# minx_ajh_1_1.net
KiCad netlist of a schematic drawn in EAGLE
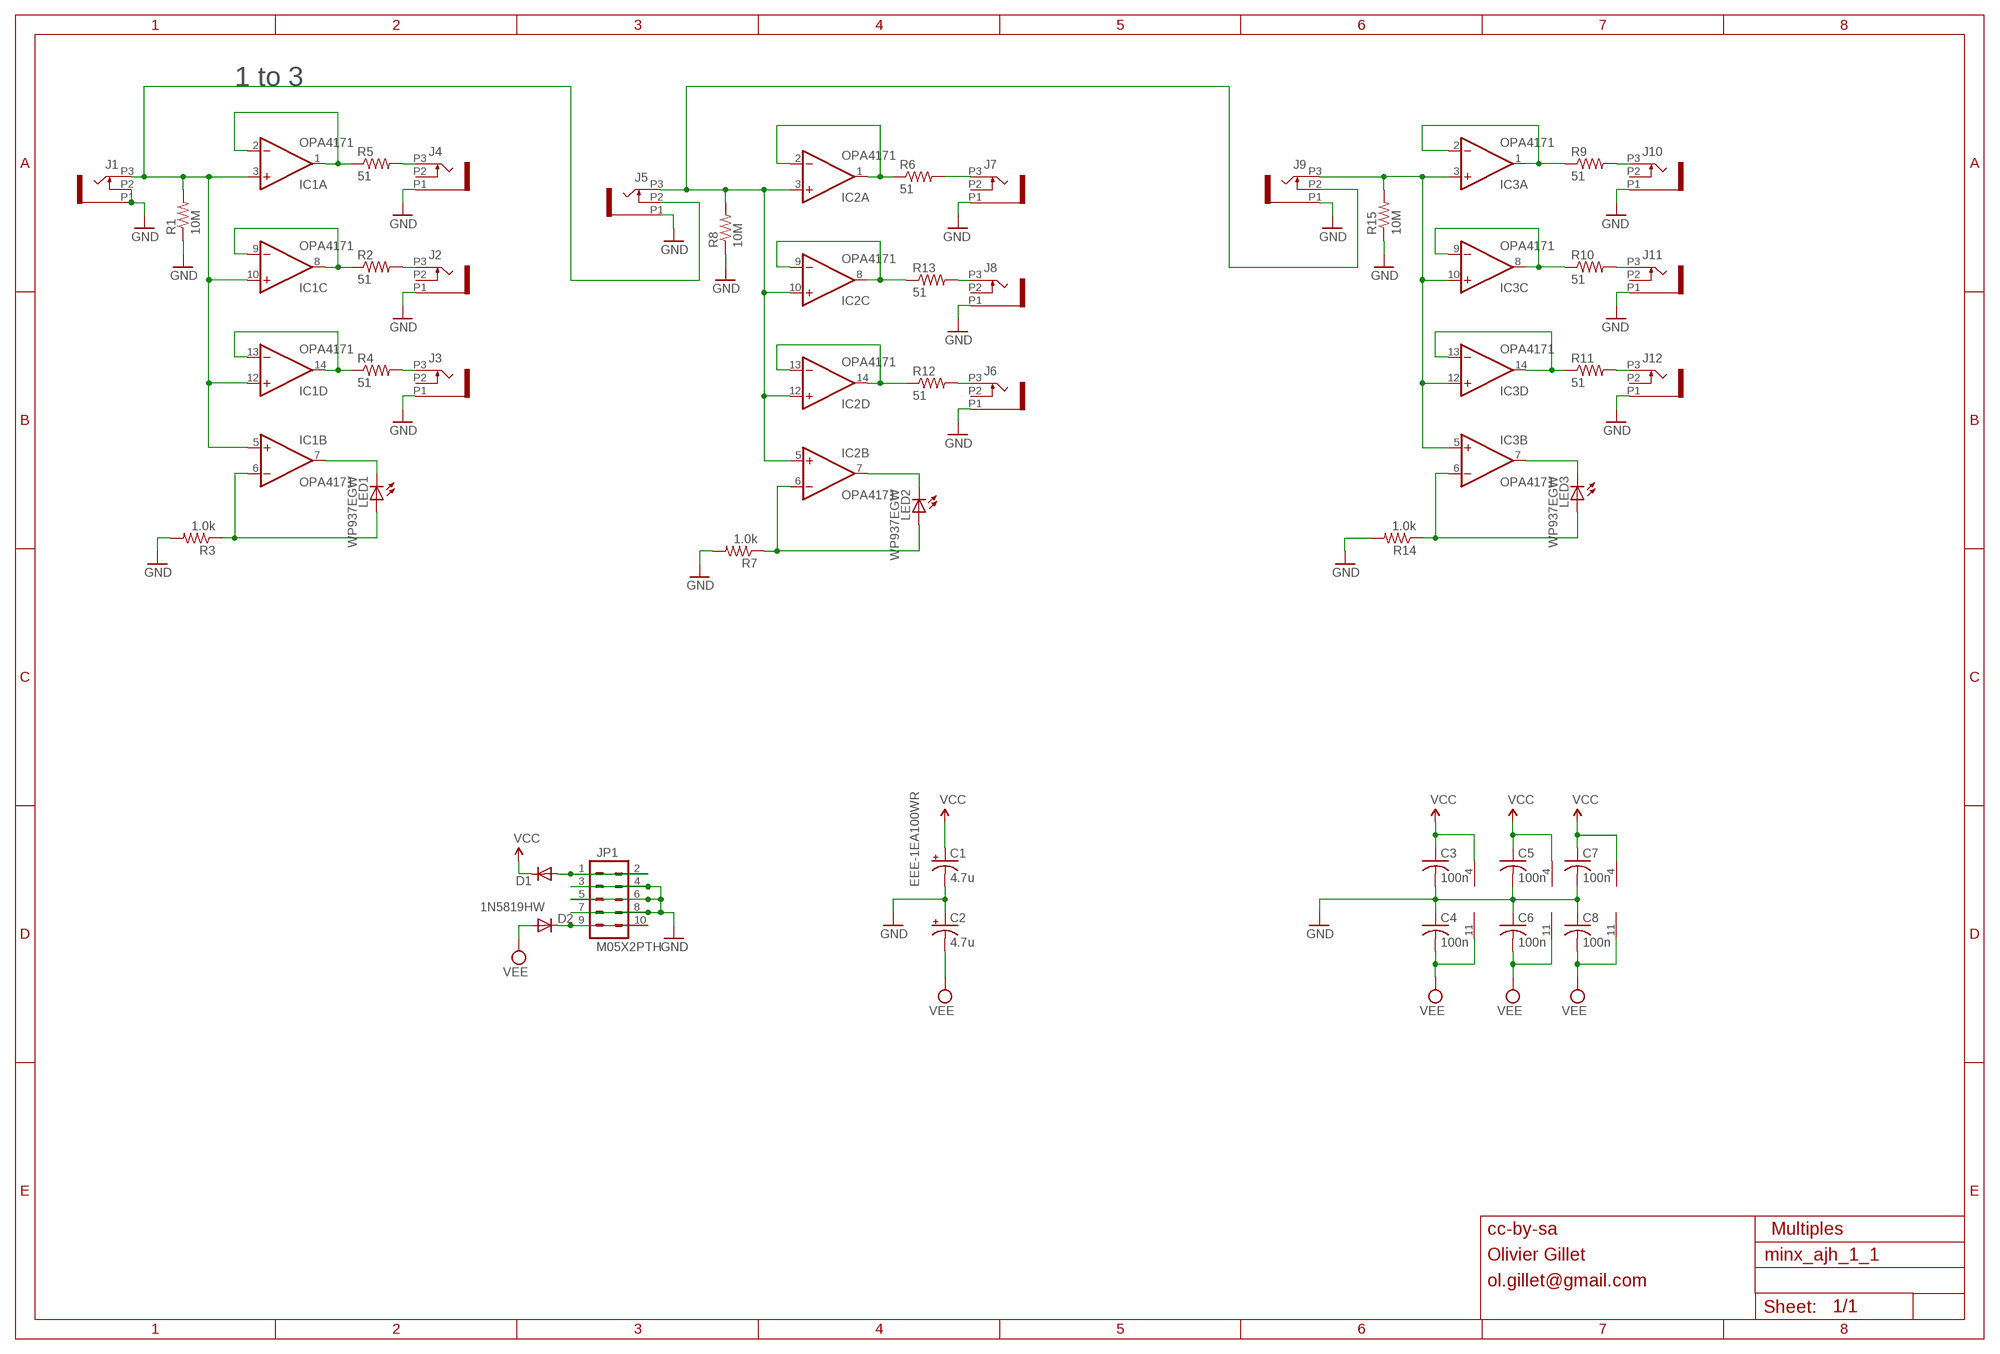
[diagram p0: schematic, sheet 1]

(export (version "E")
  (design (tool "Eeschema 10.0.6"))
  (components
    (comp (ref "C1")
      (value "4.7u")
      (footprint "eagle-import:PANASONIC_A")
      (libsource (lib "eagle-import") (part "CPOL-USA"))
    )
    (comp (ref "C2")
      (value "4.7u")
      (footprint "eagle-import:PANASONIC_A")
      (libsource (lib "eagle-import") (part "CPOL-USA"))
    )
    (comp (ref "C3")
      (value "100n")
      (footprint "eagle-import:C0603")
      (libsource (lib "eagle-import") (part "C-USC0603"))
    )
    (comp (ref "C4")
      (value "100n")
      (footprint "eagle-import:C0603")
      (libsource (lib "eagle-import") (part "C-USC0603"))
    )
    (comp (ref "C5")
      (value "100n")
      (footprint "eagle-import:C0603")
      (libsource (lib "eagle-import") (part "C-USC0603"))
    )
    (comp (ref "C6")
      (value "100n")
      (footprint "eagle-import:C0603")
      (libsource (lib "eagle-import") (part "C-USC0603"))
    )
    (comp (ref "C7")
      (value "100n")
      (footprint "eagle-import:C0603")
      (libsource (lib "eagle-import") (part "C-USC0603"))
    )
    (comp (ref "C8")
      (value "100n")
      (footprint "eagle-import:C0603")
      (libsource (lib "eagle-import") (part "C-USC0603"))
    )
    (comp (ref "D1")
      (value "1N5819HW")
      (footprint "eagle-import:SOD123")
      (libsource (lib "eagle-import") (part "DIODE-SOD123"))
    )
    (comp (ref "D2")
      (value "1N5819HW")
      (footprint "eagle-import:SOD123")
      (libsource (lib "eagle-import") (part "DIODE-SOD123"))
    )
    (comp (ref "IC1")
      (value "OPA4171")
      (footprint "eagle-import:TSSOP14")
      (libsource (lib "eagle-import") (part "TL074PW"))
    )
    (comp (ref "IC2")
      (value "OPA4171")
      (footprint "eagle-import:TSSOP14")
      (libsource (lib "eagle-import") (part "TL074PW"))
    )
    (comp (ref "IC3")
      (value "OPA4171")
      (footprint "eagle-import:TSSOP14")
      (libsource (lib "eagle-import") (part "TL074PW"))
    )
    (comp (ref "J1")
      (value "PJ301_THONKICONN6")
      (footprint "eagle-import:WQP_PJ_301M6")
      (libsource (lib "eagle-import") (part "PJ301_THONKICONN6"))
    )
    (comp (ref "J2")
      (value "PJ301_THONKICONN6")
      (footprint "eagle-import:WQP_PJ_301M6")
      (libsource (lib "eagle-import") (part "PJ301_THONKICONN6"))
    )
    (comp (ref "J3")
      (value "PJ301_THONKICONN6")
      (footprint "eagle-import:WQP_PJ_301M6")
      (libsource (lib "eagle-import") (part "PJ301_THONKICONN6"))
    )
    (comp (ref "J4")
      (value "PJ301_THONKICONN6")
      (footprint "eagle-import:WQP_PJ_301M6")
      (libsource (lib "eagle-import") (part "PJ301_THONKICONN6"))
    )
    (comp (ref "J5")
      (value "PJ301_THONKICONN6")
      (footprint "eagle-import:WQP_PJ_301M6")
      (libsource (lib "eagle-import") (part "PJ301_THONKICONN6"))
    )
    (comp (ref "J6")
      (value "PJ301_THONKICONN6")
      (footprint "eagle-import:WQP_PJ_301M6")
      (libsource (lib "eagle-import") (part "PJ301_THONKICONN6"))
    )
    (comp (ref "J7")
      (value "PJ301_THONKICONN6")
      (footprint "eagle-import:WQP_PJ_301M6")
      (libsource (lib "eagle-import") (part "PJ301_THONKICONN6"))
    )
    (comp (ref "J8")
      (value "PJ301_THONKICONN6")
      (footprint "eagle-import:WQP_PJ_301M6")
      (libsource (lib "eagle-import") (part "PJ301_THONKICONN6"))
    )
    (comp (ref "J9")
      (value "PJ301_THONKICONN6")
      (footprint "eagle-import:WQP_PJ_301M6")
      (libsource (lib "eagle-import") (part "PJ301_THONKICONN6"))
    )
    (comp (ref "J10")
      (value "PJ301_THONKICONN6")
      (footprint "eagle-import:WQP_PJ_301M6")
      (libsource (lib "eagle-import") (part "PJ301_THONKICONN6"))
    )
    (comp (ref "J11")
      (value "PJ301_THONKICONN6")
      (footprint "eagle-import:WQP_PJ_301M6")
      (libsource (lib "eagle-import") (part "PJ301_THONKICONN6"))
    )
    (comp (ref "J12")
      (value "PJ301_THONKICONN6")
      (footprint "eagle-import:WQP_PJ_301M6")
      (libsource (lib "eagle-import") (part "PJ301_THONKICONN6"))
    )
    (comp (ref "JP1")
      (value "M05X2PTH")
      (footprint "eagle-import:AVR_ICSP")
      (libsource (lib "eagle-import") (part "M05X2PTH"))
    )
    (comp (ref "LED1")
      (value "WP937EGW")
      (footprint "eagle-import:LED3MM")
      (libsource (lib "eagle-import") (part "LED3MM"))
    )
    (comp (ref "LED2")
      (value "WP937EGW")
      (footprint "eagle-import:LED3MM")
      (libsource (lib "eagle-import") (part "LED3MM"))
    )
    (comp (ref "LED3")
      (value "WP937EGW")
      (footprint "eagle-import:LED3MM")
      (libsource (lib "eagle-import") (part "LED3MM"))
    )
    (comp (ref "R1")
      (value "10M")
      (footprint "eagle-import:R0603")
      (libsource (lib "eagle-import") (part "R-US_R0603"))
    )
    (comp (ref "R2")
      (value "51")
      (footprint "eagle-import:R0603")
      (libsource (lib "eagle-import") (part "R-US_R0603"))
    )
    (comp (ref "R3")
      (value "1.0k")
      (footprint "eagle-import:R0603")
      (libsource (lib "eagle-import") (part "R-US_R0603"))
    )
    (comp (ref "R4")
      (value "51")
      (footprint "eagle-import:R0603")
      (libsource (lib "eagle-import") (part "R-US_R0603"))
    )
    (comp (ref "R5")
      (value "51")
      (footprint "eagle-import:R0603")
      (libsource (lib "eagle-import") (part "R-US_R0603"))
    )
    (comp (ref "R6")
      (value "51")
      (footprint "eagle-import:R0603")
      (libsource (lib "eagle-import") (part "R-US_R0603"))
    )
    (comp (ref "R7")
      (value "1.0k")
      (footprint "eagle-import:R0603")
      (libsource (lib "eagle-import") (part "R-US_R0603"))
    )
    (comp (ref "R8")
      (value "10M")
      (footprint "eagle-import:R0603")
      (libsource (lib "eagle-import") (part "R-US_R0603"))
    )
    (comp (ref "R9")
      (value "51")
      (footprint "eagle-import:R0603")
      (libsource (lib "eagle-import") (part "R-US_R0603"))
    )
    (comp (ref "R10")
      (value "51")
      (footprint "eagle-import:R0603")
      (libsource (lib "eagle-import") (part "R-US_R0603"))
    )
    (comp (ref "R11")
      (value "51")
      (footprint "eagle-import:R0603")
      (libsource (lib "eagle-import") (part "R-US_R0603"))
    )
    (comp (ref "R12")
      (value "51")
      (footprint "eagle-import:R0603")
      (libsource (lib "eagle-import") (part "R-US_R0603"))
    )
    (comp (ref "R13")
      (value "51")
      (footprint "eagle-import:R0603")
      (libsource (lib "eagle-import") (part "R-US_R0603"))
    )
    (comp (ref "R14")
      (value "1.0k")
      (footprint "eagle-import:R0603")
      (libsource (lib "eagle-import") (part "R-US_R0603"))
    )
    (comp (ref "R15")
      (value "10M")
      (footprint "eagle-import:R0603")
      (libsource (lib "eagle-import") (part "R-US_R0603"))
    )
  )
  (nets
    (net (code "1") (name "GND") (class "Default")
      (node (ref "C1") (pin "-") (pinfunction "-_-") (pintype "passive"))
      (node (ref "C2") (pin "+") (pinfunction "+_+") (pintype "passive"))
      (node (ref "C3") (pin "2") (pinfunction "2_2") (pintype "passive"))
      (node (ref "C4") (pin "1") (pinfunction "1_1") (pintype "passive"))
      (node (ref "C5") (pin "2") (pinfunction "2_2") (pintype "passive"))
      (node (ref "C6") (pin "1") (pinfunction "1_1") (pintype "passive"))
      (node (ref "C7") (pin "2") (pinfunction "2_2") (pintype "passive"))
      (node (ref "C8") (pin "1") (pinfunction "1_1") (pintype "passive"))
      (node (ref "J1") (pin "P1") (pinfunction "1_P1") (pintype "passive"))
      (node (ref "J1") (pin "P2") (pinfunction "2_P2") (pintype "passive"))
      (node (ref "J10") (pin "P1") (pinfunction "1_P1") (pintype "passive"))
      (node (ref "J11") (pin "P1") (pinfunction "1_P1") (pintype "passive"))
      (node (ref "J12") (pin "P1") (pinfunction "1_P1") (pintype "passive"))
      (node (ref "J2") (pin "P1") (pinfunction "1_P1") (pintype "passive"))
      (node (ref "J3") (pin "P1") (pinfunction "1_P1") (pintype "passive"))
      (node (ref "J4") (pin "P1") (pinfunction "1_P1") (pintype "passive"))
      (node (ref "J5") (pin "P1") (pinfunction "1_P1") (pintype "passive"))
      (node (ref "J6") (pin "P1") (pinfunction "1_P1") (pintype "passive"))
      (node (ref "J7") (pin "P1") (pinfunction "1_P1") (pintype "passive"))
      (node (ref "J8") (pin "P1") (pinfunction "1_P1") (pintype "passive"))
      (node (ref "J9") (pin "P1") (pinfunction "1_P1") (pintype "passive"))
      (node (ref "JP1") (pin "3") (pinfunction "3_3") (pintype "passive"))
      (node (ref "JP1") (pin "4") (pinfunction "4_4") (pintype "passive"))
      (node (ref "JP1") (pin "5") (pinfunction "5_5") (pintype "passive"))
      (node (ref "JP1") (pin "6") (pinfunction "6_6") (pintype "passive"))
      (node (ref "JP1") (pin "7") (pinfunction "7_7") (pintype "passive"))
      (node (ref "JP1") (pin "8") (pinfunction "8_8") (pintype "passive"))
      (node (ref "R1") (pin "1") (pinfunction "1_1") (pintype "passive"))
      (node (ref "R14") (pin "2") (pinfunction "2_2") (pintype "passive"))
      (node (ref "R15") (pin "1") (pinfunction "1_1") (pintype "passive"))
      (node (ref "R3") (pin "2") (pinfunction "2_2") (pintype "passive"))
      (node (ref "R7") (pin "2") (pinfunction "2_2") (pintype "passive"))
      (node (ref "R8") (pin "1") (pinfunction "1_1") (pintype "passive"))
    )
    (net (code "2") (name "Net-(D1-PadA)") (class "Default")
      (node (ref "D1") (pin "A") (pinfunction "A_A") (pintype "passive"))
      (node (ref "JP1") (pin "1") (pinfunction "1_1") (pintype "passive"))
      (node (ref "JP1") (pin "2") (pinfunction "2_2") (pintype "passive"))
    )
    (net (code "3") (name "Net-(D2-PadC)") (class "Default")
      (node (ref "D2") (pin "C") (pinfunction "C_C") (pintype "passive"))
      (node (ref "JP1") (pin "10") (pinfunction "10_10") (pintype "passive"))
      (node (ref "JP1") (pin "9") (pinfunction "9_9") (pintype "passive"))
    )
    (net (code "4") (name "Net-(IC1A-+IN)") (class "Default")
      (node (ref "IC1") (pin "10") (pinfunction "+IN_10") (pintype "input"))
      (node (ref "IC1") (pin "12") (pinfunction "+IN_12") (pintype "input"))
      (node (ref "IC1") (pin "3") (pinfunction "+IN_3") (pintype "input"))
      (node (ref "IC1") (pin "5") (pinfunction "+IN_5") (pintype "input"))
      (node (ref "J1") (pin "P3") (pinfunction "3_P3") (pintype "passive"))
      (node (ref "J5") (pin "P2") (pinfunction "2_P2") (pintype "passive"))
      (node (ref "R1") (pin "2") (pinfunction "2_2") (pintype "passive"))
    )
    (net (code "5") (name "Net-(IC1A--IN)") (class "Default")
      (node (ref "IC1") (pin "1") (pinfunction "OUT_1") (pintype "output"))
      (node (ref "IC1") (pin "2") (pinfunction "-IN_2") (pintype "input"))
      (node (ref "R5") (pin "1") (pinfunction "1_1") (pintype "passive"))
    )
    (net (code "6") (name "Net-(IC1B--IN)") (class "Default")
      (node (ref "IC1") (pin "6") (pinfunction "-IN_6") (pintype "input"))
      (node (ref "LED1") (pin "A") (pinfunction "A_A") (pintype "passive"))
      (node (ref "R3") (pin "1") (pinfunction "1_1") (pintype "passive"))
    )
    (net (code "7") (name "Net-(IC1B-OUT)") (class "Default")
      (node (ref "IC1") (pin "7") (pinfunction "OUT_7") (pintype "output"))
      (node (ref "LED1") (pin "K") (pinfunction "C_K") (pintype "passive"))
    )
    (net (code "8") (name "Net-(IC1C--IN)") (class "Default")
      (node (ref "IC1") (pin "8") (pinfunction "OUT_8") (pintype "output"))
      (node (ref "IC1") (pin "9") (pinfunction "-IN_9") (pintype "input"))
      (node (ref "R2") (pin "1") (pinfunction "1_1") (pintype "passive"))
    )
    (net (code "9") (name "Net-(IC1D--IN)") (class "Default")
      (node (ref "IC1") (pin "13") (pinfunction "-IN_13") (pintype "input"))
      (node (ref "IC1") (pin "14") (pinfunction "OUT_14") (pintype "output"))
      (node (ref "R4") (pin "1") (pinfunction "1_1") (pintype "passive"))
    )
    (net (code "10") (name "Net-(IC2A-+IN)") (class "Default")
      (node (ref "IC2") (pin "10") (pinfunction "+IN_10") (pintype "input"))
      (node (ref "IC2") (pin "12") (pinfunction "+IN_12") (pintype "input"))
      (node (ref "IC2") (pin "3") (pinfunction "+IN_3") (pintype "input"))
      (node (ref "IC2") (pin "5") (pinfunction "+IN_5") (pintype "input"))
      (node (ref "J5") (pin "P3") (pinfunction "3_P3") (pintype "passive"))
      (node (ref "J9") (pin "P2") (pinfunction "2_P2") (pintype "passive"))
      (node (ref "R8") (pin "2") (pinfunction "2_2") (pintype "passive"))
    )
    (net (code "11") (name "Net-(IC2A--IN)") (class "Default")
      (node (ref "IC2") (pin "1") (pinfunction "OUT_1") (pintype "output"))
      (node (ref "IC2") (pin "2") (pinfunction "-IN_2") (pintype "input"))
      (node (ref "R6") (pin "1") (pinfunction "1_1") (pintype "passive"))
    )
    (net (code "12") (name "Net-(IC2B--IN)") (class "Default")
      (node (ref "IC2") (pin "6") (pinfunction "-IN_6") (pintype "input"))
      (node (ref "LED2") (pin "A") (pinfunction "A_A") (pintype "passive"))
      (node (ref "R7") (pin "1") (pinfunction "1_1") (pintype "passive"))
    )
    (net (code "13") (name "Net-(IC2B-OUT)") (class "Default")
      (node (ref "IC2") (pin "7") (pinfunction "OUT_7") (pintype "output"))
      (node (ref "LED2") (pin "K") (pinfunction "C_K") (pintype "passive"))
    )
    (net (code "14") (name "Net-(IC2C--IN)") (class "Default")
      (node (ref "IC2") (pin "8") (pinfunction "OUT_8") (pintype "output"))
      (node (ref "IC2") (pin "9") (pinfunction "-IN_9") (pintype "input"))
      (node (ref "R13") (pin "1") (pinfunction "1_1") (pintype "passive"))
    )
    (net (code "15") (name "Net-(IC2D--IN)") (class "Default")
      (node (ref "IC2") (pin "13") (pinfunction "-IN_13") (pintype "input"))
      (node (ref "IC2") (pin "14") (pinfunction "OUT_14") (pintype "output"))
      (node (ref "R12") (pin "1") (pinfunction "1_1") (pintype "passive"))
    )
    (net (code "16") (name "Net-(IC3A-+IN)") (class "Default")
      (node (ref "IC3") (pin "10") (pinfunction "+IN_10") (pintype "input"))
      (node (ref "IC3") (pin "12") (pinfunction "+IN_12") (pintype "input"))
      (node (ref "IC3") (pin "3") (pinfunction "+IN_3") (pintype "input"))
      (node (ref "IC3") (pin "5") (pinfunction "+IN_5") (pintype "input"))
      (node (ref "J9") (pin "P3") (pinfunction "3_P3") (pintype "passive"))
      (node (ref "R15") (pin "2") (pinfunction "2_2") (pintype "passive"))
    )
    (net (code "17") (name "Net-(IC3A--IN)") (class "Default")
      (node (ref "IC3") (pin "1") (pinfunction "OUT_1") (pintype "output"))
      (node (ref "IC3") (pin "2") (pinfunction "-IN_2") (pintype "input"))
      (node (ref "R9") (pin "1") (pinfunction "1_1") (pintype "passive"))
    )
    (net (code "18") (name "Net-(IC3B--IN)") (class "Default")
      (node (ref "IC3") (pin "6") (pinfunction "-IN_6") (pintype "input"))
      (node (ref "LED3") (pin "A") (pinfunction "A_A") (pintype "passive"))
      (node (ref "R14") (pin "1") (pinfunction "1_1") (pintype "passive"))
    )
    (net (code "19") (name "Net-(IC3B-OUT)") (class "Default")
      (node (ref "IC3") (pin "7") (pinfunction "OUT_7") (pintype "output"))
      (node (ref "LED3") (pin "K") (pinfunction "C_K") (pintype "passive"))
    )
    (net (code "20") (name "Net-(IC3C--IN)") (class "Default")
      (node (ref "IC3") (pin "8") (pinfunction "OUT_8") (pintype "output"))
      (node (ref "IC3") (pin "9") (pinfunction "-IN_9") (pintype "input"))
      (node (ref "R10") (pin "1") (pinfunction "1_1") (pintype "passive"))
    )
    (net (code "21") (name "Net-(IC3D--IN)") (class "Default")
      (node (ref "IC3") (pin "13") (pinfunction "-IN_13") (pintype "input"))
      (node (ref "IC3") (pin "14") (pinfunction "OUT_14") (pintype "output"))
      (node (ref "R11") (pin "1") (pinfunction "1_1") (pintype "passive"))
    )
    (net (code "22") (name "Net-(J2-3)") (class "Default")
      (node (ref "J2") (pin "P3") (pinfunction "3_P3") (pintype "passive"))
      (node (ref "R2") (pin "2") (pinfunction "2_2") (pintype "passive"))
    )
    (net (code "23") (name "Net-(J3-3)") (class "Default")
      (node (ref "J3") (pin "P3") (pinfunction "3_P3") (pintype "passive"))
      (node (ref "R4") (pin "2") (pinfunction "2_2") (pintype "passive"))
    )
    (net (code "24") (name "Net-(J4-3)") (class "Default")
      (node (ref "J4") (pin "P3") (pinfunction "3_P3") (pintype "passive"))
      (node (ref "R5") (pin "2") (pinfunction "2_2") (pintype "passive"))
    )
    (net (code "25") (name "Net-(J6-3)") (class "Default")
      (node (ref "J6") (pin "P3") (pinfunction "3_P3") (pintype "passive"))
      (node (ref "R12") (pin "2") (pinfunction "2_2") (pintype "passive"))
    )
    (net (code "26") (name "Net-(J7-3)") (class "Default")
      (node (ref "J7") (pin "P3") (pinfunction "3_P3") (pintype "passive"))
      (node (ref "R6") (pin "2") (pinfunction "2_2") (pintype "passive"))
    )
    (net (code "27") (name "Net-(J8-3)") (class "Default")
      (node (ref "J8") (pin "P3") (pinfunction "3_P3") (pintype "passive"))
      (node (ref "R13") (pin "2") (pinfunction "2_2") (pintype "passive"))
    )
    (net (code "28") (name "Net-(J10-3)") (class "Default")
      (node (ref "J10") (pin "P3") (pinfunction "3_P3") (pintype "passive"))
      (node (ref "R9") (pin "2") (pinfunction "2_2") (pintype "passive"))
    )
    (net (code "29") (name "Net-(J11-3)") (class "Default")
      (node (ref "J11") (pin "P3") (pinfunction "3_P3") (pintype "passive"))
      (node (ref "R10") (pin "2") (pinfunction "2_2") (pintype "passive"))
    )
    (net (code "30") (name "Net-(J12-3)") (class "Default")
      (node (ref "J12") (pin "P3") (pinfunction "3_P3") (pintype "passive"))
      (node (ref "R11") (pin "2") (pinfunction "2_2") (pintype "passive"))
    )
    (net (code "31") (name "VCC") (class "Default")
      (node (ref "C1") (pin "+") (pinfunction "+_+") (pintype "passive"))
      (node (ref "C3") (pin "1") (pinfunction "1_1") (pintype "passive"))
      (node (ref "C5") (pin "1") (pinfunction "1_1") (pintype "passive"))
      (node (ref "C7") (pin "1") (pinfunction "1_1") (pintype "passive"))
      (node (ref "D1") (pin "C") (pinfunction "C_C") (pintype "passive"))
      (node (ref "IC1") (pin "4") (pinfunction "V+_4") (pintype "power_in"))
      (node (ref "IC2") (pin "4") (pinfunction "V+_4") (pintype "power_in"))
      (node (ref "IC3") (pin "4") (pinfunction "V+_4") (pintype "power_in"))
    )
    (net (code "32") (name "VEE") (class "Default")
      (node (ref "C2") (pin "-") (pinfunction "-_-") (pintype "passive"))
      (node (ref "C4") (pin "2") (pinfunction "2_2") (pintype "passive"))
      (node (ref "C6") (pin "2") (pinfunction "2_2") (pintype "passive"))
      (node (ref "C8") (pin "2") (pinfunction "2_2") (pintype "passive"))
      (node (ref "D2") (pin "A") (pinfunction "A_A") (pintype "passive"))
      (node (ref "IC1") (pin "11") (pinfunction "V-_11") (pintype "power_in"))
      (node (ref "IC2") (pin "11") (pinfunction "V-_11") (pintype "power_in"))
      (node (ref "IC3") (pin "11") (pinfunction "V-_11") (pintype "power_in"))
    )
    (net (code "33") (name "unconnected-(J2-2-PadP2)") (class "Default")
      (node (ref "J2") (pin "P2") (pinfunction "2_P2") (pintype "passive"))
    )
    (net (code "34") (name "unconnected-(J3-2-PadP2)") (class "Default")
      (node (ref "J3") (pin "P2") (pinfunction "2_P2") (pintype "passive"))
    )
    (net (code "35") (name "unconnected-(J4-2-PadP2)") (class "Default")
      (node (ref "J4") (pin "P2") (pinfunction "2_P2") (pintype "passive"))
    )
    (net (code "36") (name "unconnected-(J6-2-PadP2)") (class "Default")
      (node (ref "J6") (pin "P2") (pinfunction "2_P2") (pintype "passive"))
    )
    (net (code "37") (name "unconnected-(J7-2-PadP2)") (class "Default")
      (node (ref "J7") (pin "P2") (pinfunction "2_P2") (pintype "passive"))
    )
    (net (code "38") (name "unconnected-(J8-2-PadP2)") (class "Default")
      (node (ref "J8") (pin "P2") (pinfunction "2_P2") (pintype "passive"))
    )
    (net (code "39") (name "unconnected-(J10-2-PadP2)") (class "Default")
      (node (ref "J10") (pin "P2") (pinfunction "2_P2") (pintype "passive"))
    )
    (net (code "40") (name "unconnected-(J11-2-PadP2)") (class "Default")
      (node (ref "J11") (pin "P2") (pinfunction "2_P2") (pintype "passive"))
    )
    (net (code "41") (name "unconnected-(J12-2-PadP2)") (class "Default")
      (node (ref "J12") (pin "P2") (pinfunction "2_P2") (pintype "passive"))
    )
  )
)
